# PIC_Board.net
KiCad netlist of a schematic drawn in Altium Designer
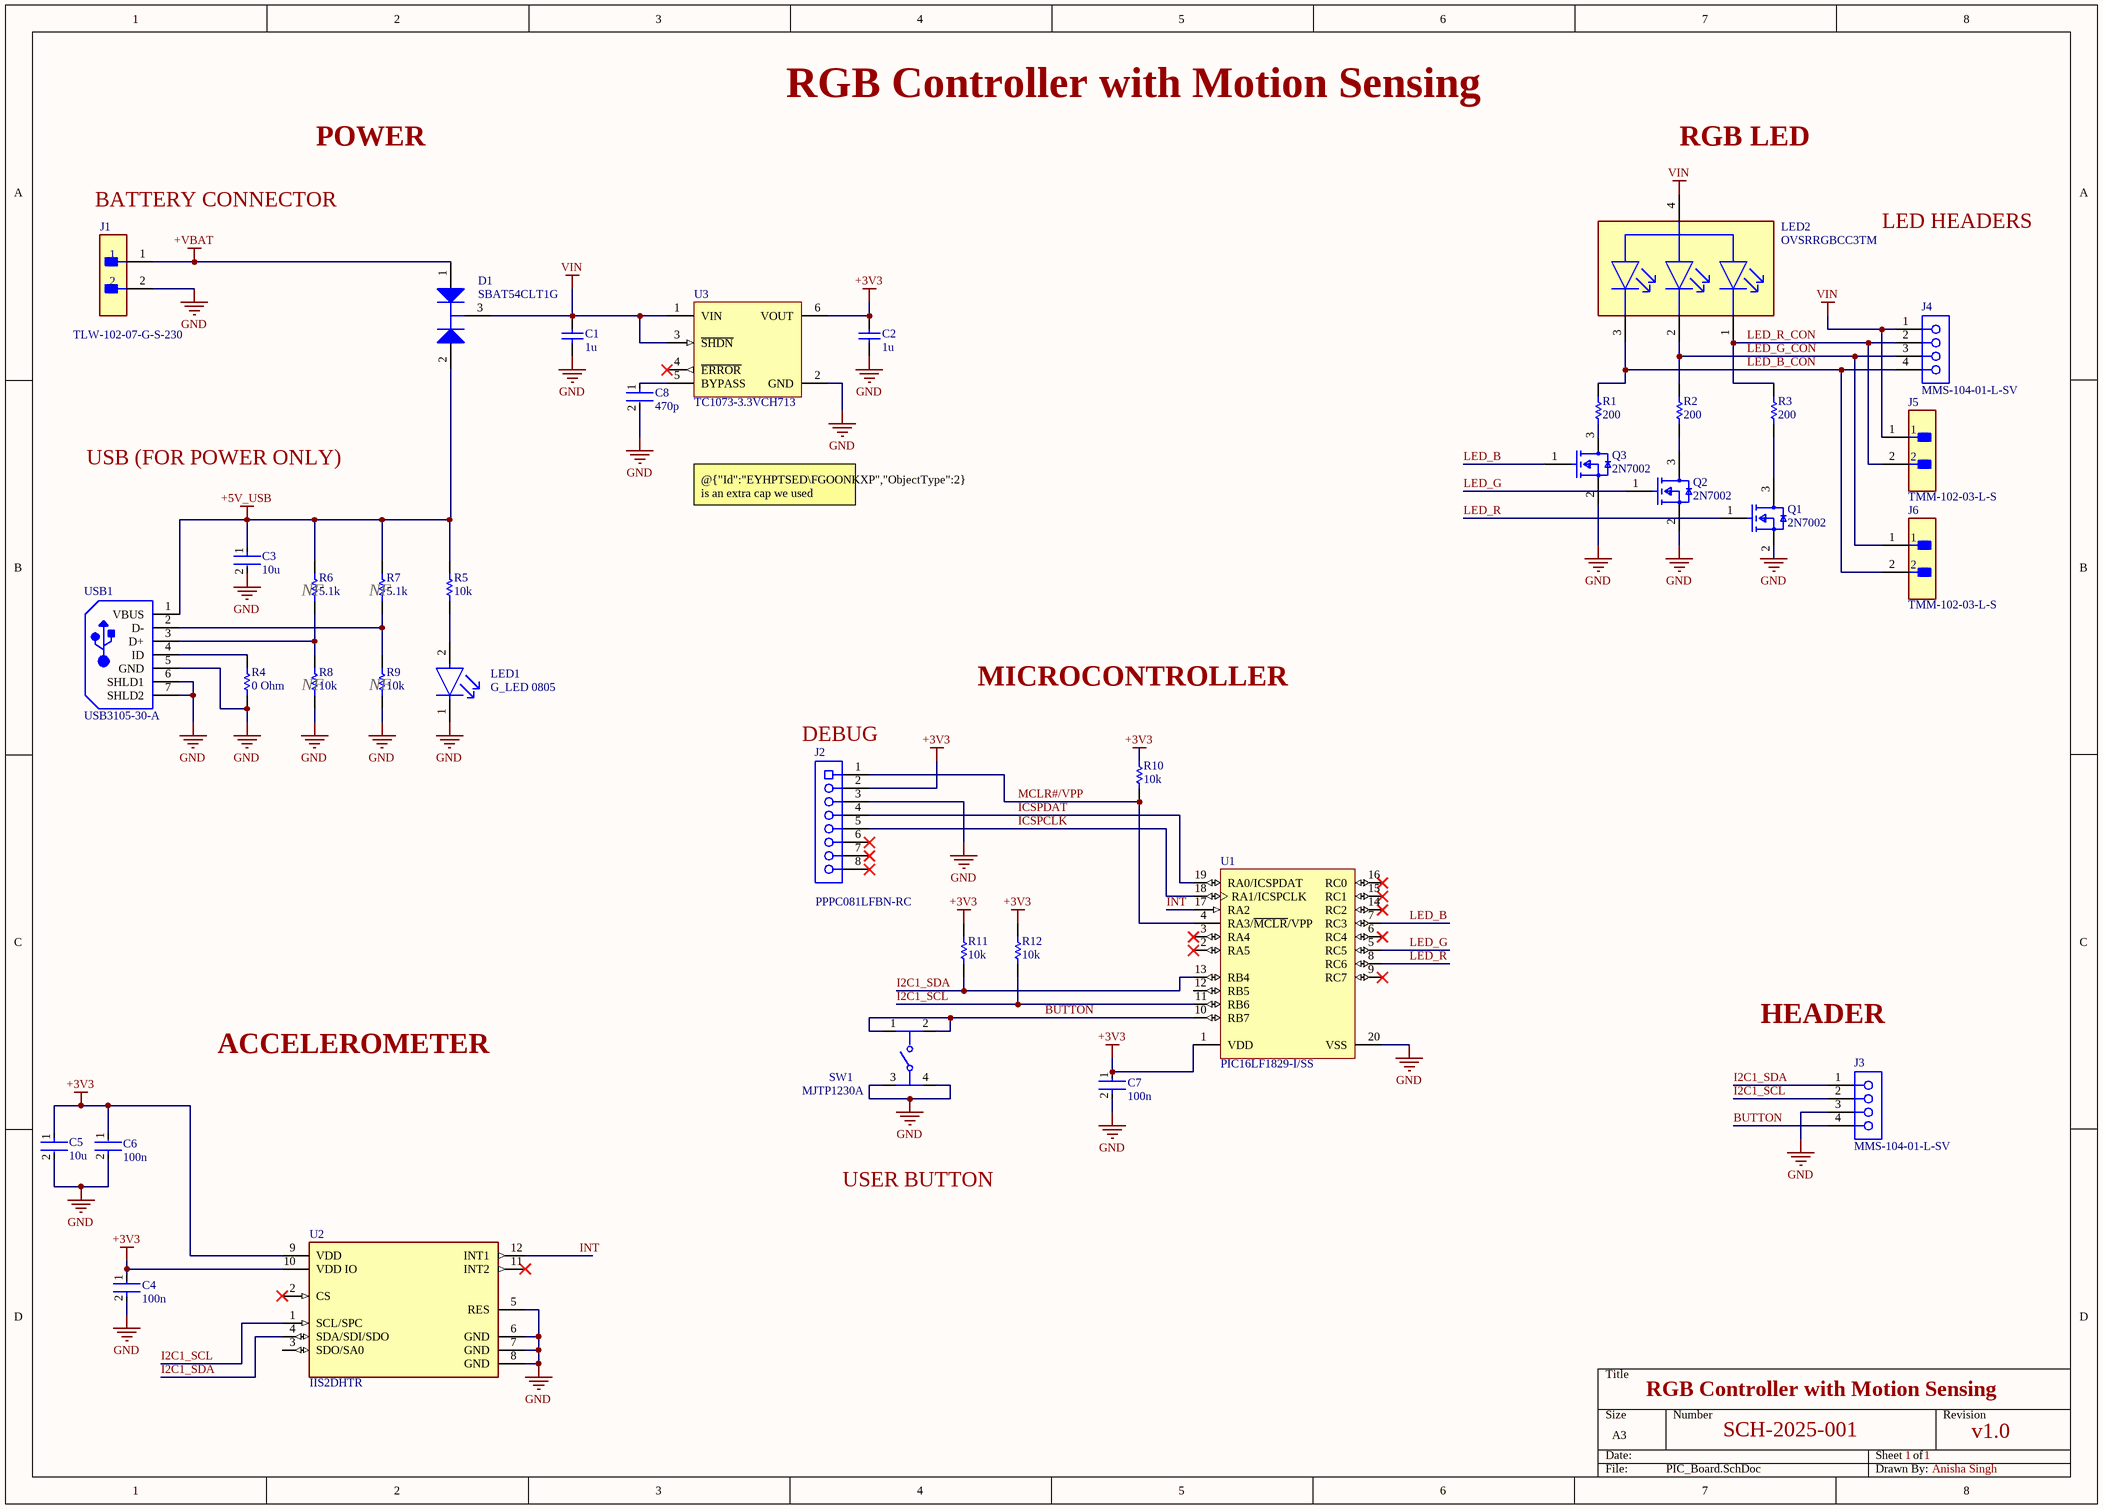
[diagram p0: PIC_Board.SchDoc]

(export (version "E")
  (design (tool "Eeschema 10.0.6"))
  (components
    (comp (ref "C1")
      (value "1u")
      (footprint "CAPC2013X140X50NL20T25")
      (fields (field (name "PART NUMBER") "C0805C105M4PACTU") (field (name "MANUFACTURER") "Kemet"))
      (libsource (lib "Altium Content Vault") (part "CAP"))
    )
    (comp (ref "C2")
      (value "1u")
      (footprint "CAPC2013X140X50NL20T25")
      (fields (field (name "PART NUMBER") "C0805C105M4PACTU") (field (name "MANUFACTURER") "Kemet"))
      (libsource (lib "Altium Content Vault") (part "CAP"))
    )
    (comp (ref "C3")
      (value "10u")
      (footprint "FP-GRM188-0_2-MFG")
      (fields (field (name "TOLERANCE") "20%"))
      (libsource (lib "Altium Content Vault") (part "11868f565c42a9108669ba33697ecf6"))
    )
    (comp (ref "C4")
      (value "100n")
      (footprint "FP-AC1210-0_85-MFG")
      (description "CAP CER 0.1UF 100V X7R 1210\r\nAC1210KKX7R0BB104")
      (fields
        (field (name "MANUFACTURER") "Yageo")
        (field (name "MANUFACTURER PART NUMBER") "AC1210KKX7R0BB104")
      )
      (libsource (lib "Altium Content Vault") (part "236180d848d6139a670b325ea6854c9"))
    )
    (comp (ref "C5")
      (value "10u")
      (footprint "FP-GRM188-0_2-MFG")
      (fields (field (name "TOLERANCE") "20%"))
      (libsource (lib "Altium Content Vault") (part "11868f565c42a9108669ba33697ecf6"))
    )
    (comp (ref "C6")
      (value "100n")
      (footprint "FP-AC1210-0_85-MFG")
      (description "CAP CER 0.1UF 100V X7R 1210\r\nAC1210KKX7R0BB104")
      (fields
        (field (name "MANUFACTURER") "Yageo")
        (field (name "MANUFACTURER PART NUMBER") "AC1210KKX7R0BB104")
      )
      (libsource (lib "Altium Content Vault") (part "236180d848d6139a670b325ea6854c9"))
    )
    (comp (ref "C7")
      (value "100n")
      (footprint "FP-AC1210-0_85-MFG")
      (description "CAP CER 0.1UF 100V X7R 1210\r\nAC1210KKX7R0BB104")
      (fields
        (field (name "MANUFACTURER") "Yageo")
        (field (name "MANUFACTURER PART NUMBER") "AC1210KKX7R0BB104")
      )
      (libsource (lib "Altium Content Vault") (part "236180d848d6139a670b325ea6854c9"))
    )
    (comp (ref "C8")
      (value "470p")
      (footprint "FP-C0402-BB-MFG")
      (description "C0402 470 pF C0G 10.00% 16 V")
      (fields (field (name "TOLERANCE") "0.1") (field (name "MANUFACTURER") "Kemet"))
      (libsource (lib "Altium Content Vault") (part "b4654b650e69147ec39a6b967a45e02"))
    )
    (comp (ref "D1")
      (value "SBAT54CLT1G")
      (footprint "ONSC-SOT-23-3-318-08_V")
      (description "Dual Common Cathode Schottky Barrier Diodes, 3-Pin SOT-23, Pb-Free, Tape and Reel")
      (fields (field (name "MANUFACTURER") "On Semiconductor"))
      (libsource (lib "Altium Content Vault") (part "ONSC-D-A1A2K3-3"))
    )
    (comp (ref "J1")
      (value "TLW-102-07-G-S-230")
      (footprint "FP-MTLW-102-07-G-S-230-MFG")
      (description "CONN HEADER VERT 2POS 2.54\r\nMMMTLW-102-07-G-S-230")
      (libsource (lib "") (part "3bc925449376181038e59eaffc5286c_1"))
    )
    (comp (ref "J2")
      (value "PPPC081LFBN-RC")
      (footprint "SLIN-PPPC081LFBN-RC_V")
      (fields (field (name "MANUFACTURER") "Sullins"))
      (libsource (lib "WePCB Projects") (part "CN-1P-F-R8"))
    )
    (comp (ref "J3")
      (value "MMS-104-01-L-SV")
      (footprint "SMTC-MMS-104-01-X-SV")
      (fields (field (name "MANUFACTURER") "Samtec"))
      (libsource (lib "Altium Content Vault") (part "SMTC-MMS-104-01-X-SV"))
    )
    (comp (ref "J4")
      (value "MMS-104-01-L-SV")
      (footprint "SMTC-MMS-104-01-X-SV")
      (fields (field (name "MANUFACTURER") "Samtec"))
      (libsource (lib "Altium Content Vault") (part "SMTC-MMS-104-01-X-SV"))
    )
    (comp (ref "J5")
      (value "TMM-102-03-L-S")
      (footprint "FP-TMM-102-03-L-S-MFG")
      (description "CONN HEADER 2POS SNGL 2MM T/H")
      (libsource (lib "Altium Content Vault") (part "3bc925449376181038e59eaffc5286c"))
    )
    (comp (ref "J6")
      (value "TMM-102-03-L-S")
      (footprint "FP-TMM-102-03-L-S-MFG")
      (description "CONN HEADER 2POS SNGL 2MM T/H")
      (libsource (lib "Altium Content Vault") (part "3bc925449376181038e59eaffc5286c"))
    )
    (comp (ref "LED1")
      (value "G_LED 0805")
      (footprint "FP-LG_R971-MFG")
      (description "LED GREEN DIFFUSED 0805 SMD\r\nQ62702P5179")
      (libsource (lib "Altium Content Vault") (part "8706943c75ba83719d021d2fdc84c58"))
    )
    (comp (ref "LED2")
      (value "OVSRRGBCC3TM")
      (footprint "FP-OVSRRGBCC3TM-MFG")
      (description "LED RGB DIFFUSED 1204 SMD")
      (libsource (lib "Altium Content Vault") (part "7312c80c6f37ed131185a1f71a63ae3"))
    )
    (comp (ref "Q1")
      (value "2N7002")
      (footprint "FP-PG-SOT23-3-MFG")
      (description "MOSFET N-CH 60V 0.3A SOT23\r\n2N7002H6327XTSA2")
      (libsource (lib "Altium Content Vault") (part "2d979dc9c009d20783d0745ce0ba7b4"))
    )
    (comp (ref "Q2")
      (value "2N7002")
      (footprint "FP-PG-SOT23-3-MFG")
      (description "MOSFET N-CH 60V 0.3A SOT23\r\n2N7002H6327XTSA2")
      (libsource (lib "Altium Content Vault") (part "2d979dc9c009d20783d0745ce0ba7b4"))
    )
    (comp (ref "Q3")
      (value "2N7002")
      (footprint "FP-PG-SOT23-3-MFG")
      (description "MOSFET N-CH 60V 0.3A SOT23\r\n2N7002H6327XTSA2")
      (libsource (lib "Altium Content Vault") (part "2d979dc9c009d20783d0745ce0ba7b4"))
    )
    (comp (ref "R1")
      (value "200")
      (footprint "RESC3225X60X45ML20T20")
      (description "CRCW1210200RJNTA")
      (fields (field (name "MANUFACTURER") "Vishay Dale"))
      (libsource (lib "Altium Content Vault") (part "RES"))
    )
    (comp (ref "R2")
      (value "200")
      (footprint "RESC3225X60X45ML20T20")
      (description "CRCW1210200RJNTA")
      (fields (field (name "MANUFACTURER") "Vishay Dale"))
      (libsource (lib "Altium Content Vault") (part "RES"))
    )
    (comp (ref "R3")
      (value "200")
      (footprint "RESC3225X60X45ML20T20")
      (description "CRCW1210200RJNTA")
      (fields (field (name "MANUFACTURER") "Vishay Dale"))
      (libsource (lib "Altium Content Vault") (part "RES"))
    )
    (comp (ref "R4")
      (value "0 Ohm")
      (footprint "RESC3116X65X45LL15T20")
      (fields (field (name "MANUFACTURER") "TE Connectivity") (field (name "TOLERANCE") "0%"))
      (libsource (lib "Altium Content Vault") (part "RES-2"))
    )
    (comp (ref "R5")
      (value "10k")
      (footprint "RESC1005X40X20NL05T10")
      (description "TNPW040210K0DEED")
      (fields (field (name "MANUFACTURER") "Vishay BCcomponents"))
      (libsource (lib "Altium Content Vault") (part "RES"))
    )
    (comp (ref "R6")
      (value "5.1k")
      (footprint "RESC1005X35X20LL05T10")
      (description "CPF0402B5K1E1")
      (fields (field (name "MANUFACTURER") "TE Connectivity / AMP"))
      (libsource (lib "Altium Content Vault") (part "RES"))
    )
    (comp (ref "R7")
      (value "5.1k")
      (footprint "RESC1005X35X20LL05T10")
      (description "CPF0402B5K1E1")
      (fields (field (name "MANUFACTURER") "TE Connectivity / AMP"))
      (libsource (lib "Altium Content Vault") (part "RES"))
    )
    (comp (ref "R8")
      (value "10k")
      (footprint "RESC1005X40X20NL05T10")
      (description "TNPW040210K0DEED")
      (fields (field (name "MANUFACTURER") "Vishay BCcomponents"))
      (libsource (lib "Altium Content Vault") (part "RES"))
    )
    (comp (ref "R9")
      (value "10k")
      (footprint "RESC1005X40X20NL05T10")
      (description "TNPW040210K0DEED")
      (fields (field (name "MANUFACTURER") "Vishay BCcomponents"))
      (libsource (lib "Altium Content Vault") (part "RES"))
    )
    (comp (ref "R10")
      (value "10k")
      (footprint "RESC1005X40X20NL05T10")
      (description "TNPW040210K0DEED")
      (fields (field (name "MANUFACTURER") "Vishay BCcomponents"))
      (libsource (lib "Altium Content Vault") (part "RES"))
    )
    (comp (ref "R11")
      (value "10k")
      (footprint "RESC1005X40X20NL05T10")
      (description "TNPW040210K0DEED")
      (fields (field (name "MANUFACTURER") "Vishay BCcomponents"))
      (libsource (lib "Altium Content Vault") (part "RES"))
    )
    (comp (ref "R12")
      (value "10k")
      (footprint "RESC1005X40X20NL05T10")
      (description "TNPW040210K0DEED")
      (fields (field (name "MANUFACTURER") "Vishay BCcomponents"))
      (libsource (lib "Altium Content Vault") (part "RES"))
    )
    (comp (ref "SW1")
      (value "MJTP1230A")
      (footprint "FP-MJTP1230A-MFG")
      (description "SWITCH TACTILE SPST-NO 0.05A 12V")
      (libsource (lib "Altium Content Vault") (part "1adf0dd01260c80cf25a44bfd6b99ba"))
    )
    (comp (ref "U1")
      (value "PIC16LF1829-I/SS")
      (footprint "MCHP-SSOP-SS20_L")
      (fields (field (name "MANUFACTURER") "Microchip"))
      (libsource (lib "Altium Content Vault") (part "MCHP-PIC16F150X_182X-20"))
    )
    (comp (ref "U2")
      (value "IIS2DHTR")
      (footprint "FP-LGA-12-8365767-MFG")
      (description "ACCEL 2-16G I2C/SPI 12LGA")
      (fields
        (field (name "MANUFACTURER") "STMicroelectronics")
        (field (name "OCTOPART") "https://octopart.com/iis2dhtr-stmicroelectronics-58218805")
      )
      (libsource (lib "Altium Content Vault") (part "0aa3afda2c658fffe6312583959f072"))
    )
    (comp (ref "U3")
      (value "TC1073-3.3VCH713")
      (footprint "SOT-23-CH6_M")
      (libsource (lib "Altium Content Vault") (part "PM-LINEREG-TC1072-IL6"))
    )
    (comp (ref "USB1")
      (value "USB3105-30-A")
      (footprint "GCT-USB3105-30-A_V")
      (description "USB 2.0 A/B Receptacle, 30 V, -55 to 85 degC, 5-Pin THD, RoHS, Tape and Reel")
      (fields (field (name "MANUFACTURER") "Global Connector Technology"))
      (libsource (lib "Altium Content Vault") (part "USB-5-2SHLD"))
    )
  )
  (nets
    (net (code "1") (name "+3V3") (class "Default")
      (node (ref "C2") (pin "2") (pinfunction "2_2") (pintype "passive"))
      (node (ref "C4") (pin "1") (pinfunction "1_1") (pintype "passive"))
      (node (ref "C5") (pin "1") (pinfunction "1_1") (pintype "passive"))
      (node (ref "C6") (pin "1") (pinfunction "1_1") (pintype "passive"))
      (node (ref "C7") (pin "1") (pinfunction "1_1") (pintype "passive"))
      (node (ref "J2") (pin "2") (pinfunction "2_2") (pintype "passive"))
      (node (ref "R10") (pin "2") (pinfunction "2_2") (pintype "passive"))
      (node (ref "R11") (pin "2") (pinfunction "2_2") (pintype "passive"))
      (node (ref "R12") (pin "2") (pinfunction "2_2") (pintype "passive"))
      (node (ref "U1") (pin "1") (pinfunction "VDD_1") (pintype "power_in"))
      (node (ref "U2") (pin "10") (pinfunction "VDD_IO_10") (pintype "power_in"))
      (node (ref "U2") (pin "9") (pinfunction "VDD_9") (pintype "power_in"))
      (node (ref "U3") (pin "6") (pinfunction "VOUT_6") (pintype "power_in"))
    )
    (net (code "2") (name "+5V_USB") (class "Default")
      (node (ref "C3") (pin "1") (pinfunction "1_1") (pintype "passive"))
      (node (ref "D1") (pin "2") (pinfunction "A2_2") (pintype "passive"))
      (node (ref "R5") (pin "2") (pinfunction "2_2") (pintype "passive"))
      (node (ref "R6") (pin "2") (pinfunction "2_2") (pintype "passive"))
      (node (ref "R7") (pin "2") (pinfunction "2_2") (pintype "passive"))
      (node (ref "USB1") (pin "1") (pinfunction "VBUS_1") (pintype "passive"))
    )
    (net (code "3") (name "+VBAT") (class "Default")
      (node (ref "D1") (pin "1") (pinfunction "A1_1") (pintype "passive"))
      (node (ref "J1") (pin "1") (pinfunction "1_1") (pintype "passive"))
    )
    (net (code "4") (name "/BUTTON") (class "Default")
      (node (ref "J3") (pin "4") (pinfunction "4_4") (pintype "passive"))
      (node (ref "SW1") (pin "1") (pinfunction "1_1") (pintype "passive"))
      (node (ref "SW1") (pin "2") (pinfunction "2_2") (pintype "passive"))
      (node (ref "U1") (pin "10") (pinfunction "RB7_10") (pintype "bidirectional"))
    )
    (net (code "5") (name "/I2C1_SCL") (class "Default")
      (node (ref "J3") (pin "2") (pinfunction "2_2") (pintype "passive"))
      (node (ref "R12") (pin "1") (pinfunction "1_1") (pintype "passive"))
      (node (ref "U1") (pin "11") (pinfunction "RB6_11") (pintype "bidirectional"))
      (node (ref "U2") (pin "1") (pinfunction "SCL/SPC_1") (pintype "input"))
    )
    (net (code "6") (name "/I2C1_SDA") (class "Default")
      (node (ref "J3") (pin "1") (pinfunction "1_1") (pintype "passive"))
      (node (ref "R11") (pin "1") (pinfunction "1_1") (pintype "passive"))
      (node (ref "U1") (pin "13") (pinfunction "RB4_13") (pintype "bidirectional"))
      (node (ref "U2") (pin "4") (pinfunction "SDA/SDI/SDO_4") (pintype "bidirectional"))
    )
    (net (code "7") (name "/ICSPCLK") (class "Default")
      (node (ref "J2") (pin "5") (pinfunction "5_5") (pintype "passive"))
      (node (ref "U1") (pin "18") (pinfunction "RA1/ICSPCLK_18") (pintype "bidirectional"))
    )
    (net (code "8") (name "/ICSPDAT") (class "Default")
      (node (ref "J2") (pin "4") (pinfunction "4_4") (pintype "passive"))
      (node (ref "U1") (pin "19") (pinfunction "RA0/ICSPDAT_19") (pintype "bidirectional"))
    )
    (net (code "9") (name "/INT") (class "Default")
      (node (ref "U1") (pin "17") (pinfunction "RA2_17") (pintype "input"))
      (node (ref "U2") (pin "12") (pinfunction "INT1_12") (pintype "output"))
    )
    (net (code "10") (name "/LED_B") (class "Default")
      (node (ref "Q3") (pin "1") (pinfunction "gate_1") (pintype "passive"))
      (node (ref "U1") (pin "7") (pinfunction "RC3_7") (pintype "bidirectional"))
    )
    (net (code "11") (name "/LED_B_CON") (class "Default")
      (node (ref "J4") (pin "4") (pinfunction "4_4") (pintype "passive"))
      (node (ref "J6") (pin "2") (pinfunction "2_2") (pintype "passive"))
      (node (ref "LED2") (pin "3") (pinfunction "B_3") (pintype "passive"))
      (node (ref "R1") (pin "2") (pinfunction "2_2") (pintype "passive"))
    )
    (net (code "12") (name "/LED_G") (class "Default")
      (node (ref "Q2") (pin "1") (pinfunction "gate_1") (pintype "passive"))
      (node (ref "U1") (pin "5") (pinfunction "RC5_5") (pintype "bidirectional"))
    )
    (net (code "13") (name "/LED_G_CON") (class "Default")
      (node (ref "J4") (pin "3") (pinfunction "3_3") (pintype "passive"))
      (node (ref "J6") (pin "1") (pinfunction "1_1") (pintype "passive"))
      (node (ref "LED2") (pin "2") (pinfunction "G_2") (pintype "passive"))
      (node (ref "R2") (pin "2") (pinfunction "2_2") (pintype "passive"))
    )
    (net (code "14") (name "/LED_R") (class "Default")
      (node (ref "Q1") (pin "1") (pinfunction "gate_1") (pintype "passive"))
      (node (ref "U1") (pin "8") (pinfunction "RC6_8") (pintype "bidirectional"))
    )
    (net (code "15") (name "/LED_R_CON") (class "Default")
      (node (ref "J4") (pin "2") (pinfunction "2_2") (pintype "passive"))
      (node (ref "J5") (pin "2") (pinfunction "2_2") (pintype "passive"))
      (node (ref "LED2") (pin "1") (pinfunction "R_1") (pintype "passive"))
      (node (ref "R3") (pin "2") (pinfunction "2_2") (pintype "passive"))
    )
    (net (code "16") (name "/MCLR#{slash}VPP") (class "Default")
      (node (ref "J2") (pin "1") (pinfunction "1_1") (pintype "passive"))
      (node (ref "R10") (pin "1") (pinfunction "1_1") (pintype "passive"))
      (node (ref "U1") (pin "4") (pinfunction "RA3/~{MCLR}/VPP_4") (pintype "passive"))
    )
    (net (code "17") (name "GND") (class "Default")
      (node (ref "C1") (pin "1") (pinfunction "1_1") (pintype "passive"))
      (node (ref "C2") (pin "1") (pinfunction "1_1") (pintype "passive"))
      (node (ref "C3") (pin "2") (pinfunction "2_2") (pintype "passive"))
      (node (ref "C4") (pin "2") (pinfunction "2_2") (pintype "passive"))
      (node (ref "C5") (pin "2") (pinfunction "2_2") (pintype "passive"))
      (node (ref "C6") (pin "2") (pinfunction "2_2") (pintype "passive"))
      (node (ref "C7") (pin "2") (pinfunction "2_2") (pintype "passive"))
      (node (ref "C8") (pin "2") (pinfunction "2_2") (pintype "passive"))
      (node (ref "J1") (pin "2") (pinfunction "2_2") (pintype "passive"))
      (node (ref "J2") (pin "3") (pinfunction "3_3") (pintype "passive"))
      (node (ref "J3") (pin "3") (pinfunction "3_3") (pintype "passive"))
      (node (ref "LED1") (pin "1") (pinfunction "C_1") (pintype "passive"))
      (node (ref "Q1") (pin "2") (pinfunction "source_2") (pintype "passive"))
      (node (ref "Q2") (pin "2") (pinfunction "source_2") (pintype "passive"))
      (node (ref "Q3") (pin "2") (pinfunction "source_2") (pintype "passive"))
      (node (ref "R4") (pin "1") (pinfunction "1_1") (pintype "passive"))
      (node (ref "R8") (pin "1") (pinfunction "1_1") (pintype "passive"))
      (node (ref "R9") (pin "1") (pinfunction "1_1") (pintype "passive"))
      (node (ref "SW1") (pin "3") (pinfunction "3_3") (pintype "passive"))
      (node (ref "SW1") (pin "4") (pinfunction "4_4") (pintype "passive"))
      (node (ref "U1") (pin "20") (pinfunction "VSS_20") (pintype "power_in"))
      (node (ref "U2") (pin "5") (pinfunction "RES_5") (pintype "passive"))
      (node (ref "U2") (pin "6") (pinfunction "GND_6") (pintype "power_in"))
      (node (ref "U2") (pin "7") (pinfunction "GND_7") (pintype "power_in"))
      (node (ref "U2") (pin "8") (pinfunction "GND_8") (pintype "power_in"))
      (node (ref "U3") (pin "2") (pinfunction "GND_2") (pintype "power_in"))
      (node (ref "USB1") (pin "5") (pinfunction "GND_5") (pintype "passive"))
      (node (ref "USB1") (pin "6") (pinfunction "SHLD1_6") (pintype "passive"))
      (node (ref "USB1") (pin "7") (pinfunction "SHLD2_7") (pintype "passive"))
    )
    (net (code "18") (name "Net-(LED1-A)") (class "Default")
      (node (ref "LED1") (pin "2") (pinfunction "A_2") (pintype "passive"))
      (node (ref "R5") (pin "1") (pinfunction "1_1") (pintype "passive"))
    )
    (net (code "19") (name "Net-(Q1-drain)") (class "Default")
      (node (ref "Q1") (pin "3") (pinfunction "drain_3") (pintype "passive"))
      (node (ref "R3") (pin "1") (pinfunction "1_1") (pintype "passive"))
    )
    (net (code "20") (name "Net-(Q2-drain)") (class "Default")
      (node (ref "Q2") (pin "3") (pinfunction "drain_3") (pintype "passive"))
      (node (ref "R2") (pin "1") (pinfunction "1_1") (pintype "passive"))
    )
    (net (code "21") (name "Net-(Q3-drain)") (class "Default")
      (node (ref "Q3") (pin "3") (pinfunction "drain_3") (pintype "passive"))
      (node (ref "R1") (pin "1") (pinfunction "1_1") (pintype "passive"))
    )
    (net (code "22") (name "Net-(U3-BYPASS)") (class "Default")
      (node (ref "C8") (pin "1") (pinfunction "1_1") (pintype "passive"))
      (node (ref "U3") (pin "5") (pinfunction "BYPASS_5") (pintype "passive"))
    )
    (net (code "23") (name "Net-(USB1-D+)") (class "Default")
      (node (ref "R6") (pin "1") (pinfunction "1_1") (pintype "passive"))
      (node (ref "R8") (pin "2") (pinfunction "2_2") (pintype "passive"))
      (node (ref "USB1") (pin "3") (pinfunction "D+_3") (pintype "passive"))
    )
    (net (code "24") (name "Net-(USB1-D-)") (class "Default")
      (node (ref "R7") (pin "1") (pinfunction "1_1") (pintype "passive"))
      (node (ref "R9") (pin "2") (pinfunction "2_2") (pintype "passive"))
      (node (ref "USB1") (pin "2") (pinfunction "D-_2") (pintype "passive"))
    )
    (net (code "25") (name "Net-(USB1-ID)") (class "Default")
      (node (ref "R4") (pin "2") (pinfunction "2_2") (pintype "passive"))
      (node (ref "USB1") (pin "4") (pinfunction "ID_4") (pintype "passive"))
    )
    (net (code "26") (name "VIN") (class "Default")
      (node (ref "C1") (pin "2") (pinfunction "2_2") (pintype "passive"))
      (node (ref "D1") (pin "3") (pinfunction "K_3") (pintype "passive"))
      (node (ref "J4") (pin "1") (pinfunction "1_1") (pintype "passive"))
      (node (ref "J5") (pin "1") (pinfunction "1_1") (pintype "passive"))
      (node (ref "LED2") (pin "4") (pinfunction "ANODE_4") (pintype "passive"))
      (node (ref "U3") (pin "1") (pinfunction "VIN_1") (pintype "power_in"))
      (node (ref "U3") (pin "3") (pinfunction "~{SHDN}_3") (pintype "input"))
    )
    (net (code "27") (name "unconnected-(J2-Pad6)") (class "Default")
      (node (ref "J2") (pin "6") (pinfunction "6_6") (pintype "passive+no_connect"))
    )
    (net (code "28") (name "unconnected-(J2-Pad7)") (class "Default")
      (node (ref "J2") (pin "7") (pinfunction "7_7") (pintype "passive+no_connect"))
    )
    (net (code "29") (name "unconnected-(J2-Pad8)") (class "Default")
      (node (ref "J2") (pin "8") (pinfunction "8_8") (pintype "passive+no_connect"))
    )
    (net (code "30") (name "unconnected-(U1-RA4-Pad3)") (class "Default")
      (node (ref "U1") (pin "3") (pinfunction "RA4_3") (pintype "bidirectional+no_connect"))
    )
    (net (code "31") (name "unconnected-(U1-RA5-Pad2)") (class "Default")
      (node (ref "U1") (pin "2") (pinfunction "RA5_2") (pintype "bidirectional+no_connect"))
    )
    (net (code "32") (name "unconnected-(U1-RB5-Pad12)") (class "Default")
      (node (ref "U1") (pin "12") (pinfunction "RB5_12") (pintype "bidirectional"))
    )
    (net (code "33") (name "unconnected-(U1-RC0-Pad16)") (class "Default")
      (node (ref "U1") (pin "16") (pinfunction "RC0_16") (pintype "bidirectional+no_connect"))
    )
    (net (code "34") (name "unconnected-(U1-RC1-Pad15)") (class "Default")
      (node (ref "U1") (pin "15") (pinfunction "RC1_15") (pintype "bidirectional+no_connect"))
    )
    (net (code "35") (name "unconnected-(U1-RC2-Pad14)") (class "Default")
      (node (ref "U1") (pin "14") (pinfunction "RC2_14") (pintype "bidirectional+no_connect"))
    )
    (net (code "36") (name "unconnected-(U1-RC4-Pad6)") (class "Default")
      (node (ref "U1") (pin "6") (pinfunction "RC4_6") (pintype "bidirectional+no_connect"))
    )
    (net (code "37") (name "unconnected-(U1-RC7-Pad9)") (class "Default")
      (node (ref "U1") (pin "9") (pinfunction "RC7_9") (pintype "bidirectional+no_connect"))
    )
    (net (code "38") (name "unconnected-(U2-CS-Pad2)") (class "Default")
      (node (ref "U2") (pin "2") (pinfunction "CS_2") (pintype "input+no_connect"))
    )
    (net (code "39") (name "unconnected-(U2-INT2-Pad11)") (class "Default")
      (node (ref "U2") (pin "11") (pinfunction "INT2_11") (pintype "output+no_connect"))
    )
    (net (code "40") (name "unconnected-(U2-SDO{slash}SA0-Pad3)") (class "Default")
      (node (ref "U2") (pin "3") (pinfunction "SDO/SA0_3") (pintype "bidirectional"))
    )
    (net (code "41") (name "unconnected-(U3-~{ERROR}-Pad4)") (class "Default")
      (node (ref "U3") (pin "4") (pinfunction "~{ERROR}_4") (pintype "output+no_connect"))
    )
  )
)
